# Complete_Power_Supply.net
KiCad netlist of a schematic drawn in Altium Designer
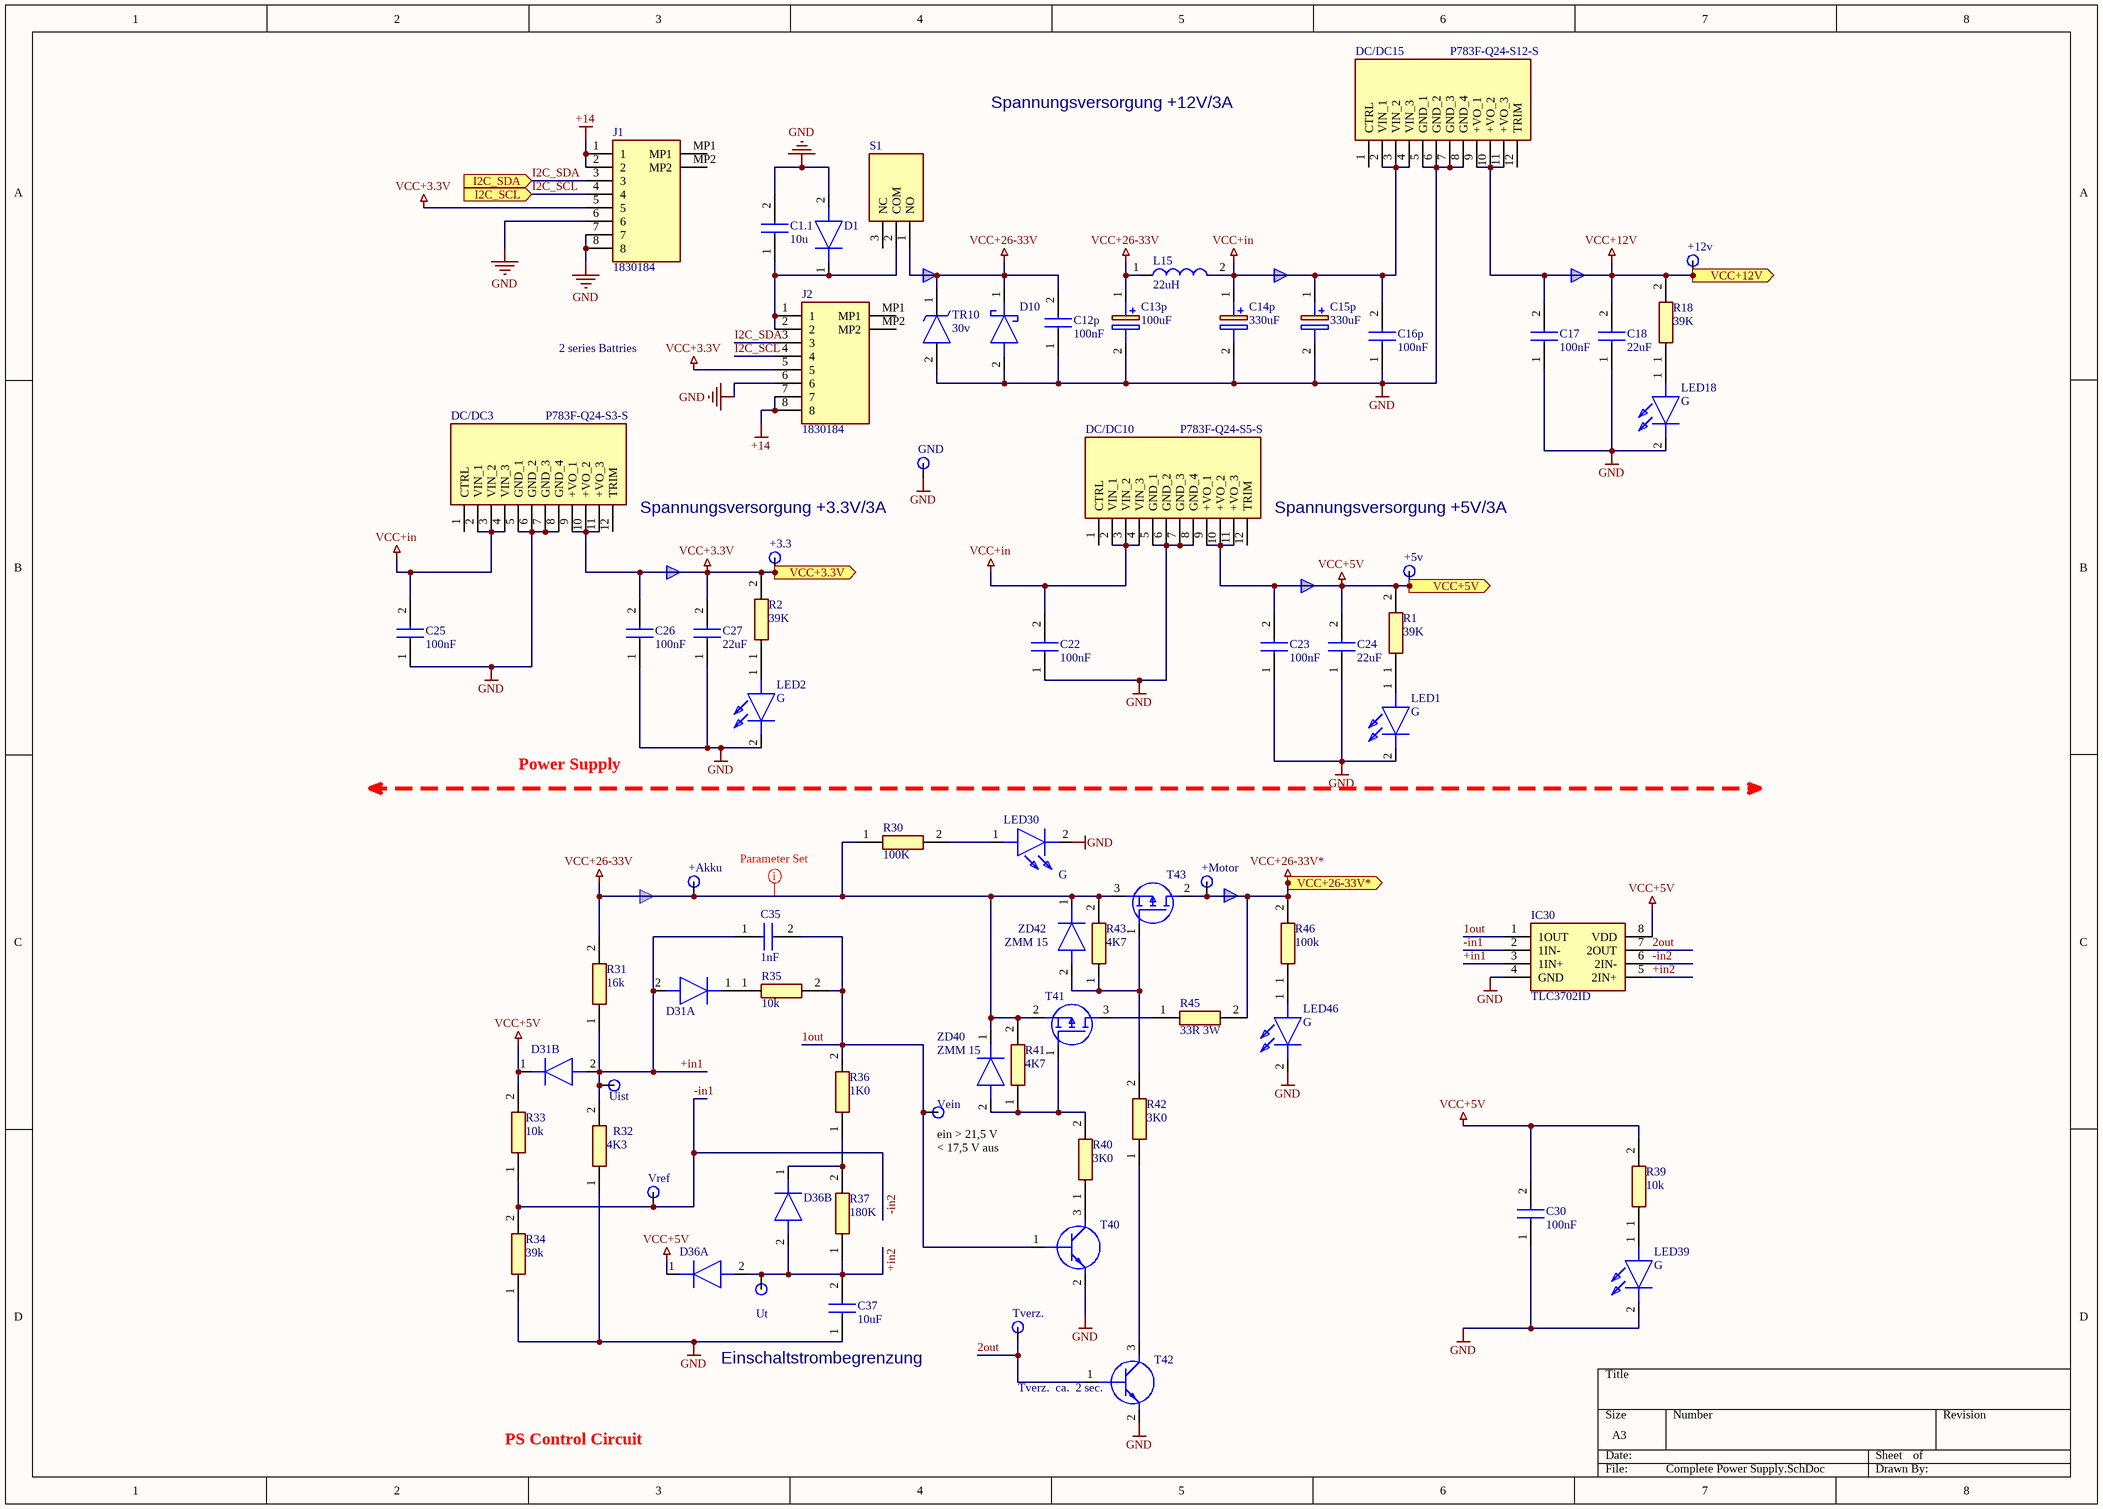
[diagram p0: Complete Power Supply.SchDoc]

(export (version "E")
  (design (tool "Eeschema 10.0.6"))
  (components
    (comp (ref "+3.3") (value "TP") (footprint "TP") (libsource (lib "tp sch lib") (part "TP")))
    (comp (ref "+5v") (value "TP") (footprint "TP") (libsource (lib "tp sch lib") (part "TP")))
    (comp (ref "+12v") (value "TP") (footprint "TP") (libsource (lib "tp sch lib") (part "TP")))
    (comp (ref "+Akku") (value "TP") (footprint "TP") (libsource (lib "tp sch lib") (part "TP")))
    (comp (ref "+Motor") (value "TP") (footprint "TP") (libsource (lib "tp sch lib") (part "TP")))
    (comp (ref "C1.1")
      (value "10u")
      (footprint "SamacSys:CAPC3216X180N")
      (description "Capacitor\r\nCL31A106KBHNNNE")
      (fields
        (field (name "MANUFACTURER_PART_NUMBER") "CL31A106KBHNNNE")
        (field (name "MOUSER PART NUMBER") "187-CL31A106KBHNNNE")
      )
      (libsource (lib "*") (part "CL31A106KBHNNNE"))
    )
    (comp (ref "C12p")
      (value "100nF")
      (footprint "SamacSys:CAPC1608X90N")
      (description "Capacitor\r\nGRM188R61E225KA12D\r\n0603")
      (fields
        (field (name "MANUFACTURER_PART_NUMBER") "GRM188R61E225KA12D")
        (field (name "MOUSER PART NUMBER") "81-GRM188R61E225KA2D")
      )
      (libsource (lib "SamacSys") (part "GRM188R61E225KA12D"))
    )
    (comp (ref "C13p")
      (value "100uF")
      (footprint "SamacSys:CAPPRD350W50D800H1750")
      (description "Capacitor Polarised")
      (fields (field (name "MANUFACTURER_PART_NUMBER") "860080274012"))
      (libsource (lib "*") (part "860080274012"))
    )
    (comp (ref "C14p")
      (value "330uF")
      (footprint "SamacSys:CAPPRD500W60D1050H1750")
      (description "Capacitor Polarised")
      (fields (field (name "MANUFACTURER_PART_NUMBER") "25YXF470M10X16"))
      (libsource (lib "*") (part "25YXF470M10X16"))
    )
    (comp (ref "C15p")
      (value "330uF")
      (footprint "SamacSys:CAPPRD500W60D1050H1750")
      (description "Capacitor Polarised")
      (fields (field (name "MANUFACTURER_PART_NUMBER") "25YXF470M10X16"))
      (libsource (lib "*") (part "25YXF470M10X16"))
    )
    (comp (ref "C16p")
      (value "100nF")
      (footprint "SamacSys:CAPC1608X90N")
      (description "Capacitor\r\nGRM188R61E225KA12D\r\n0603")
      (fields
        (field (name "MANUFACTURER_PART_NUMBER") "GRM188R61E225KA12D")
        (field (name "MOUSER PART NUMBER") "81-GRM188R61E225KA2D")
      )
      (libsource (lib "SamacSys") (part "GRM188R61E225KA12D"))
    )
    (comp (ref "C17")
      (value "100nF")
      (footprint "SamacSys:CAPC1608X90N")
      (description "Capacitor\r\nGRM188R61E225KA12D\r\n0603")
      (fields
        (field (name "MANUFACTURER_PART_NUMBER") "GRM188R61E225KA12D")
        (field (name "MOUSER PART NUMBER") "81-GRM188R61E225KA2D")
      )
      (libsource (lib "SamacSys") (part "GRM188R61E225KA12D"))
    )
    (comp (ref "C18")
      (value "22uF")
      (footprint "SamacSys:CAPC3216X180N")
      (description "Capacitor\r\nGRM31CR61H106MA12L\r\n1206")
      (fields
        (field (name "MANUFACTURER_PART_NUMBER") "GRM31CR61H106MA12L")
        (field (name "MOUSER PART NUMBER") "81-GRM31CR61H106MA2L")
      )
      (libsource (lib "SamacSys") (part "GRM31CR61H106MA12L"))
    )
    (comp (ref "C22")
      (value "100nF")
      (footprint "SamacSys:CAPC1608X90N")
      (description "Capacitor\r\nGRM188R61E225KA12D\r\n0603")
      (fields
        (field (name "MANUFACTURER_PART_NUMBER") "GRM188R61E225KA12D")
        (field (name "MOUSER PART NUMBER") "81-GRM188R61E225KA2D")
      )
      (libsource (lib "SamacSys") (part "GRM188R61E225KA12D"))
    )
    (comp (ref "C23")
      (value "100nF")
      (footprint "SamacSys:CAPC1608X90N")
      (description "Capacitor\r\nGRM188R61E225KA12D\r\n0603")
      (fields
        (field (name "MANUFACTURER_PART_NUMBER") "GRM188R61E225KA12D")
        (field (name "MOUSER PART NUMBER") "81-GRM188R61E225KA2D")
      )
      (libsource (lib "SamacSys") (part "GRM188R61E225KA12D"))
    )
    (comp (ref "C24")
      (value "22uF")
      (footprint "SamacSys:CAPC3216X180N")
      (description "Capacitor\r\nGRM31CR61H106MA12L\r\n1206")
      (fields
        (field (name "MANUFACTURER_PART_NUMBER") "GRM31CR61H106MA12L")
        (field (name "MOUSER PART NUMBER") "81-GRM31CR61H106MA2L")
      )
      (libsource (lib "SamacSys") (part "GRM31CR61H106MA12L"))
    )
    (comp (ref "C25")
      (value "100nF")
      (footprint "SamacSys:CAPC1608X90N")
      (description "Capacitor\r\nGRM188R61E225KA12D\r\n0603")
      (fields
        (field (name "MANUFACTURER_PART_NUMBER") "GRM188R61E225KA12D")
        (field (name "MOUSER PART NUMBER") "81-GRM188R61E225KA2D")
      )
      (libsource (lib "SamacSys") (part "GRM188R61E225KA12D"))
    )
    (comp (ref "C26")
      (value "100nF")
      (footprint "SamacSys:CAPC1608X90N")
      (description "Capacitor\r\nGRM188R61E225KA12D\r\n0603")
      (fields
        (field (name "MANUFACTURER_PART_NUMBER") "GRM188R61E225KA12D")
        (field (name "MOUSER PART NUMBER") "81-GRM188R61E225KA2D")
      )
      (libsource (lib "SamacSys") (part "GRM188R61E225KA12D"))
    )
    (comp (ref "C27")
      (value "22uF")
      (footprint "SamacSys:CAPC3216X180N")
      (description "Capacitor\r\nGRM31CR61H106MA12L\r\n1206")
      (fields
        (field (name "MANUFACTURER_PART_NUMBER") "GRM31CR61H106MA12L")
        (field (name "MOUSER PART NUMBER") "81-GRM31CR61H106MA2L")
      )
      (libsource (lib "SamacSys") (part "GRM31CR61H106MA12L"))
    )
    (comp (ref "C30")
      (value "100nF")
      (footprint "SamacSys:CAPC1608X90N")
      (description "Capacitor\r\nGRM188R61E225KA12D\r\n0603")
      (fields
        (field (name "MANUFACTURER_PART_NUMBER") "GRM188R61E225KA12D")
        (field (name "MOUSER PART NUMBER") "81-GRM188R61E225KA2D")
      )
      (libsource (lib "SamacSys") (part "GRM188R61E225KA12D"))
    )
    (comp (ref "C35")
      (value "1nF")
      (footprint "SamacSys:CAPC1608X90N")
      (description "Capacitor\r\nGRM188R61E225KA12D\r\n0603")
      (fields
        (field (name "MANUFACTURER_PART_NUMBER") "GRM188R61E225KA12D")
        (field (name "MOUSER PART NUMBER") "81-GRM188R61E225KA2D")
      )
      (libsource (lib "SamacSys") (part "GRM188R61E225KA12D"))
    )
    (comp (ref "C37")
      (value "10uF")
      (footprint "SamacSys:CAPC1608X90N")
      (description "Capacitor\r\nGRM188R61E225KA12D\r\n0603")
      (fields
        (field (name "MANUFACTURER_PART_NUMBER") "GRM188R61E225KA12D")
        (field (name "MOUSER PART NUMBER") "81-GRM188R61E225KA2D")
      )
      (libsource (lib "SamacSys") (part "GRM188R61E225KA12D"))
    )
    (comp (ref "D1")
      (value "SM6T39A")
      (footprint "SamacSys:SMBJ36CATR")
      (description "Diode")
      (fields (field (name "MOUSER PART NUMBER") "511-SM6T39A"))
      (libsource (lib "*") (part "SM6T39A"))
    )
    (comp (ref "D10")
      (value "~")
      (footprint "SamacSys:DIOM8059X295N")
      (description "Schottky Diode\r\n30BQ015TR")
      (fields (field (name "MANUFACTURER_PART_NUMBER") "30BQ015TR"))
      (libsource (lib "*") (part "30BQ015TR"))
    )
    (comp (ref "D31A")
      (value "BAS3010A03WE6327HTSA1")
      (footprint "SamacSys:SOD2513X110N")
      (description "Diode")
      (fields (field (name "MOUSER PART NUMBER") "726-BAS3010A-03WE6"))
      (libsource (lib "*") (part "BAS3010A03WE6327HTSA1"))
    )
    (comp (ref "D31B")
      (value "BAS3010A03WE6327HTSA1")
      (footprint "SamacSys:SOD2513X110N")
      (description "Diode")
      (fields (field (name "MOUSER PART NUMBER") "726-BAS3010A-03WE6"))
      (libsource (lib "*") (part "BAS3010A03WE6327HTSA1"))
    )
    (comp (ref "D36A")
      (value "BAS3010A03WE6327HTSA1")
      (footprint "SamacSys:SOD2513X110N")
      (description "Diode")
      (fields (field (name "MOUSER PART NUMBER") "726-BAS3010A-03WE6"))
      (libsource (lib "*") (part "BAS3010A03WE6327HTSA1"))
    )
    (comp (ref "D36B")
      (value "BAS3010A03WE6327HTSA1")
      (footprint "SamacSys:SOD2513X110N")
      (description "Diode")
      (fields (field (name "MOUSER PART NUMBER") "726-BAS3010A-03WE6"))
      (libsource (lib "*") (part "BAS3010A03WE6327HTSA1"))
    )
    (comp (ref "DC/DC3")
      (value "P783F-Q24-S3-S")
      (footprint "SamacSys:P783FQ24S12S")
      (description "Power Supply\r\nP783F-Q24-S12-S")
      (fields
        (field (name "MANUFACTURER_PART_NUMBER") "P783F-Q24-S12-S")
        (field (name "MOUSER PART NUMBER") "490-P783F-Q24-S12-S")
      )
      (libsource (lib "*") (part "P783F-Q24-S12-S"))
    )
    (comp (ref "DC/DC10")
      (value "P783F-Q24-S5-S")
      (footprint "SamacSys:P783FQ24S12S")
      (description "Power Supply\r\nP783F-Q24-S12-S")
      (fields
        (field (name "MANUFACTURER_PART_NUMBER") "P783F-Q24-S12-S")
        (field (name "MOUSER PART NUMBER") "490-P783F-Q24-S12-S")
      )
      (libsource (lib "*") (part "P783F-Q24-S12-S"))
    )
    (comp (ref "DC/DC15")
      (value "P783F-Q24-S12-S")
      (footprint "SamacSys:P783FQ24S12S")
      (description "Power Supply\r\nP783F-Q24-S12-S")
      (fields (field (name "MOUSER PART NUMBER") "490-P783F-Q24-S12-S"))
      (libsource (lib "*") (part "P783F-Q24-S12-S"))
    )
    (comp (ref "GND") (value "TP") (footprint "TP") (libsource (lib "tp sch lib") (part "TP")))
    (comp (ref "IC30")
      (value "TLC3702ID")
      (footprint "SamacSys:SOIC127P600X175-8N")
      (description "Integrated Circuit")
      (fields (field (name "MOUSER PART NUMBER") "595-TLC3702ID"))
      (libsource (lib "*") (part "TLC3702ID"))
    )
    (comp (ref "J1")
      (value "1830184")
      (footprint "SamacSys:1830184")
      (description "Connector")
      (fields (field (name "MOUSER PART NUMBER") "651-1830184"))
      (libsource (lib "*") (part "1830184"))
    )
    (comp (ref "J2")
      (value "1830184")
      (footprint "SamacSys:1830184")
      (description "Connector")
      (fields (field (name "MOUSER PART NUMBER") "651-1830184"))
      (libsource (lib "*") (part "1830184"))
    )
    (comp (ref "L15")
      (value "22uH")
      (footprint "SamacSys:INDPM7366X300N")
      (description "Inductor")
      (fields
        (field (name "MANUFACTURER_PART_NUMBER") "74437346068")
        (field (name "MOUSER PART NUMBER") "710-74437346068")
      )
      (libsource (lib "*") (part "74437346068"))
    )
    (comp (ref "LED1")
      (value "G")
      (footprint "SamacSys:KP2012SGD")
      (description "LED\r\nKP-2012SGD\r\n0805")
      (fields (field (name "MANUFACTURER_PART_NUMBER") "KP-2012SGD"))
      (libsource (lib "*") (part "KP-2012SGD"))
    )
    (comp (ref "LED2")
      (value "G")
      (footprint "SamacSys:KP2012SGD")
      (description "LED\r\nKP-2012SGD\r\n0805")
      (fields (field (name "MANUFACTURER_PART_NUMBER") "KP-2012SGD"))
      (libsource (lib "*") (part "KP-2012SGD"))
    )
    (comp (ref "LED18")
      (value "G")
      (footprint "SamacSys:KP2012SGD")
      (description "LED\r\nKP-2012SGD\r\n0805")
      (fields (field (name "MANUFACTURER_PART_NUMBER") "KP-2012SGD"))
      (libsource (lib "*") (part "KP-2012SGD"))
    )
    (comp (ref "LED30")
      (value "G")
      (footprint "SamacSys:KP2012SGD")
      (description "LED\r\nKP-2012SGD\r\n0805")
      (fields (field (name "MANUFACTURER_PART_NUMBER") "KP-2012SGD"))
      (libsource (lib "*") (part "KP-2012SGD"))
    )
    (comp (ref "LED39")
      (value "G")
      (footprint "SamacSys:KP2012SGD")
      (description "LED\r\nKP-2012SGD\r\n0805")
      (fields (field (name "MANUFACTURER_PART_NUMBER") "KP-2012SGD"))
      (libsource (lib "*") (part "KP-2012SGD"))
    )
    (comp (ref "LED46")
      (value "G")
      (footprint "SamacSys:KP2012SGD")
      (description "LED\r\nKP-2012SGD\r\n0805")
      (fields (field (name "MANUFACTURER_PART_NUMBER") "KP-2012SGD"))
      (libsource (lib "*") (part "KP-2012SGD"))
    )
    (comp (ref "R1")
      (value "39K")
      (footprint "SamacSys:RESC2012X65N")
      (description "Resistor\r\nCPF0805B100RE1\r\n0805")
      (fields
        (field (name "MANUFACTURER_PART_NUMBER") "CPF0805B100RE1")
        (field (name "MOUSER PART NUMBER") "279-CPF0805B100RE1")
      )
      (libsource (lib "") (part "CPF0805B100RE1_1"))
    )
    (comp (ref "R2")
      (value "39K")
      (footprint "SamacSys:RESC2012X65N")
      (description "Resistor\r\nCPF0805B100RE1\r\n0805")
      (fields
        (field (name "MANUFACTURER_PART_NUMBER") "CPF0805B100RE1")
        (field (name "MOUSER PART NUMBER") "279-CPF0805B100RE1")
      )
      (libsource (lib "") (part "CPF0805B100RE1_1"))
    )
    (comp (ref "R18")
      (value "39K")
      (footprint "SamacSys:RESC2012X65N")
      (description "Resistor\r\nCPF0805B100RE1\r\n0805")
      (fields
        (field (name "MANUFACTURER_PART_NUMBER") "CPF0805B100RE1")
        (field (name "MOUSER PART NUMBER") "279-CPF0805B100RE1")
      )
      (libsource (lib "") (part "CPF0805B100RE1_1"))
    )
    (comp (ref "R30")
      (value "100K")
      (footprint "SamacSys:RESC2012X65N")
      (description "Resistor\r\nCPF0805B100RE1\r\n0805")
      (fields
        (field (name "MANUFACTURER_PART_NUMBER") "CPF0805B100RE1")
        (field (name "MOUSER PART NUMBER") "279-CPF0805B100RE1")
      )
      (libsource (lib "*") (part "CPF0805B100RE1"))
    )
    (comp (ref "R31")
      (value "16k")
      (footprint "SamacSys:RESC1608X60N")
      (description "Resistor\r\n0603")
      (fields (field (name "MANUFACTURER_PART_NUMBER") "MCSR06X47R0FTL"))
      (libsource (lib "SamacSys") (part "MCSR06X47R0FTL"))
    )
    (comp (ref "R32")
      (value "4K3")
      (footprint "SamacSys:RESC1608X60N")
      (description "Resistor\r\n0603")
      (fields (field (name "MANUFACTURER_PART_NUMBER") "MCSR06X47R0FTL"))
      (libsource (lib "SamacSys") (part "MCSR06X47R0FTL"))
    )
    (comp (ref "R33")
      (value "10k")
      (footprint "SamacSys:RESC1608X60N")
      (description "Resistor\r\n0603")
      (fields (field (name "MANUFACTURER_PART_NUMBER") "MCSR06X47R0FTL"))
      (libsource (lib "SamacSys") (part "MCSR06X47R0FTL"))
    )
    (comp (ref "R34")
      (value "39k")
      (footprint "SamacSys:RESC1608X60N")
      (description "Resistor\r\n0603")
      (fields (field (name "MANUFACTURER_PART_NUMBER") "MCSR06X47R0FTL"))
      (libsource (lib "SamacSys") (part "MCSR06X47R0FTL"))
    )
    (comp (ref "R35")
      (value "10k")
      (footprint "SamacSys:RESC1608X60N")
      (description "Resistor\r\n0603")
      (fields (field (name "MANUFACTURER_PART_NUMBER") "MCSR06X47R0FTL"))
      (libsource (lib "") (part "MCSR06X47R0FTL_1"))
    )
    (comp (ref "R36")
      (value "1K0")
      (footprint "SamacSys:RESC1608X60N")
      (description "Resistor\r\n0603")
      (fields (field (name "MANUFACTURER_PART_NUMBER") "MCSR06X47R0FTL"))
      (libsource (lib "SamacSys") (part "MCSR06X47R0FTL"))
    )
    (comp (ref "R37")
      (value "180K")
      (footprint "SamacSys:RESC1608X60N")
      (description "Resistor\r\n0603")
      (fields (field (name "MANUFACTURER_PART_NUMBER") "MCSR06X47R0FTL"))
      (libsource (lib "SamacSys") (part "MCSR06X47R0FTL"))
    )
    (comp (ref "R39")
      (value "10k")
      (footprint "SamacSys:RESC2012X65N")
      (description "Resistor\r\nCPF0805B100RE1\r\n0805")
      (fields
        (field (name "MANUFACTURER_PART_NUMBER") "CPF0805B100RE1")
        (field (name "MOUSER PART NUMBER") "279-CPF0805B100RE1")
      )
      (libsource (lib "") (part "CPF0805B100RE1_1"))
    )
    (comp (ref "R40")
      (value "3K0")
      (footprint "SamacSys:RESC1608X60N")
      (description "Resistor\r\n0603")
      (fields (field (name "MANUFACTURER_PART_NUMBER") "MCSR06X47R0FTL"))
      (libsource (lib "SamacSys") (part "MCSR06X47R0FTL"))
    )
    (comp (ref "R41")
      (value "4K7")
      (footprint "SamacSys:RESC1608X60N")
      (description "Resistor\r\n0603")
      (fields (field (name "MANUFACTURER_PART_NUMBER") "MCSR06X47R0FTL"))
      (libsource (lib "SamacSys") (part "MCSR06X47R0FTL"))
    )
    (comp (ref "R42")
      (value "3K0")
      (footprint "SamacSys:RESC1608X60N")
      (description "Resistor\r\n0603")
      (fields (field (name "MANUFACTURER_PART_NUMBER") "MCSR06X47R0FTL"))
      (libsource (lib "SamacSys") (part "MCSR06X47R0FTL"))
    )
    (comp (ref "R43")
      (value "4K7")
      (footprint "SamacSys:RESC1608X60N")
      (description "Resistor\r\n0603")
      (fields (field (name "MANUFACTURER_PART_NUMBER") "MCSR06X47R0FTL"))
      (libsource (lib "SamacSys") (part "MCSR06X47R0FTL"))
    )
    (comp (ref "R45")
      (value "33R 3W")
      (footprint "SamacSys:ERJ8_B_BW_R_LW_CW_D")
      (description "Resistor\r\n1206\r\n33R 3W")
      (fields
        (field (name "MANUFACTURER_PART_NUMBER") "ERJ-8BWFR075V")
        (field (name "MOUSER PART NUMBER") "667-ERJ-8BWFR075V")
      )
      (libsource (lib "SamacSys") (part "ERJ-8BWFR075V"))
    )
    (comp (ref "R46")
      (value "100k")
      (footprint "SamacSys:RESC2012X65N")
      (description "Resistor\r\nCPF0805B100RE1\r\n0805")
      (fields
        (field (name "MANUFACTURER_PART_NUMBER") "CPF0805B100RE1")
        (field (name "MOUSER PART NUMBER") "279-CPF0805B100RE1")
      )
      (libsource (lib "") (part "CPF0805B100RE1_1"))
    )
    (comp (ref "S1")
      (value "1-1825137-1")
      (footprint "SamacSys:118251371")
      (description "Switch single pole single throw")
      (libsource (lib "*") (part "1-1825137-1"))
    )
    (comp (ref "T40")
      (value "BCR135WH6327XTSA1")
      (footprint "SamacSys:SOT65P210X100-3N")
      (description "Digitaltransistor, npn, 50V, 100mA, SOT23")
      (fields (field (name "MOUSER PART NUMBER") "726-BCR135WH6327XTSA"))
      (libsource (lib "*") (part "BCR135WH6327XTSA1"))
    )
    (comp (ref "T41")
      (value "AO3407A")
      (footprint "SamacSys:SOT95P280X125-3N")
      (description "MOS-FET, p-Kanal, -40  V, -3,4 A, SOT23")
      (libsource (lib "*") (part "AO3407A"))
    )
    (comp (ref "T42")
      (value "BCR135WH6327XTSA1")
      (footprint "SamacSys:SOT65P210X100-3N")
      (description "Digitaltransistor, npn, 50V, 100mA, SOT23")
      (fields (field (name "MOUSER PART NUMBER") "726-BCR135WH6327XTSA"))
      (libsource (lib "*") (part "BCR135WH6327XTSA1"))
    )
    (comp (ref "T43")
      (value "AUIRF9Z34N")
      (footprint "SamacSys:TO254P482X1016X2192-3P")
      (description "MOS-FET, p-Kanal, -40  V, -120 A, TO220")
      (fields (field (name "MOUSER PART NUMBER") "942-AUIRF9Z34N"))
      (libsource (lib "*") (part "AUIRF9Z34N"))
    )
    (comp (ref "TR10")
      (value "30v")
      (footprint "SamacSys:DIOM7959X262N")
      (description "Überspannungsdiode, 30 V, 3000 W, DO214-AB, unidirektional, SMD")
      (fields
        (field (name "MANUFACTURER_PART_NUMBER") "1.5SMC15A")
        (field (name "MOUSER PART NUMBER") "576-1.5SMC15A")
      )
      (libsource (lib "*") (part "1.5SMC15A"))
    )
    (comp (ref "Tverz.") (value "TP") (footprint "TP") (libsource (lib "tp sch lib") (part "TP")))
    (comp (ref "Uist") (value "TP") (footprint "TP") (libsource (lib "tp sch lib") (part "TP")))
    (comp (ref "Ut") (value "TP") (footprint "TP") (libsource (lib "tp sch lib") (part "TP")))
    (comp (ref "Vein") (value "TP") (footprint "TP") (libsource (lib "tp sch lib") (part "TP")))
    (comp (ref "Vref") (value "TP") (footprint "TP") (libsource (lib "tp sch lib") (part "TP")))
    (comp (ref "ZD40")
      (value "ZMM 15")
      (footprint "SamacSys:BZT55B13GS08")
      (description "SOD-80\r\nZMM 15, 5%")
      (fields
        (field (name "MANUFACTURER_PART_NUMBER") "LS4150GS08")
        (field (name "MOUSER PART NUMBER") "78-LS4150")
      )
      (libsource (lib "*") (part "LS4150GS08"))
    )
    (comp (ref "ZD42")
      (value "ZMM 15")
      (footprint "SamacSys:BZT55B13GS08")
      (description "SOD-80\r\nZMM 15, 5%")
      (fields
        (field (name "MANUFACTURER_PART_NUMBER") "LS4150GS08")
        (field (name "MOUSER PART NUMBER") "78-LS4150")
      )
      (libsource (lib "*") (part "LS4150GS08"))
    )
  )
  (nets
    (net (code "1") (name "+14") (class "Default")
      (node (ref "J1") (pin "1") (pinfunction "1_1") (pintype "passive"))
      (node (ref "J1") (pin "2") (pinfunction "2_2") (pintype "passive"))
      (node (ref "J2") (pin "7") (pinfunction "7_7") (pintype "passive"))
      (node (ref "J2") (pin "8") (pinfunction "8_8") (pintype "passive"))
    )
    (net (code "2") (name "/+in1") (class "Default")
      (node (ref "C35") (pin "1") (pinfunction "1_1") (pintype "passive"))
      (node (ref "D31A") (pin "2") (pinfunction "A_2") (pintype "passive"))
      (node (ref "D31B") (pin "2") (pinfunction "A_2") (pintype "passive"))
      (node (ref "IC30") (pin "3") (pinfunction "1IN+_3") (pintype "passive"))
      (node (ref "R31") (pin "1") (pinfunction "1_1") (pintype "passive"))
      (node (ref "R32") (pin "2") (pinfunction "2_2") (pintype "passive"))
      (node (ref "Uist") (pin "25") (pinfunction "25_25") (pintype "passive"))
    )
    (net (code "3") (name "/+in2") (class "Default")
      (node (ref "C37") (pin "2") (pinfunction "2_2") (pintype "passive"))
      (node (ref "D36A") (pin "2") (pinfunction "A_2") (pintype "passive"))
      (node (ref "D36B") (pin "2") (pinfunction "A_2") (pintype "passive"))
      (node (ref "IC30") (pin "5") (pinfunction "2IN+_5") (pintype "passive"))
      (node (ref "R37") (pin "1") (pinfunction "1_1") (pintype "passive"))
      (node (ref "Ut") (pin "25") (pinfunction "25_25") (pintype "passive"))
    )
    (net (code "4") (name "/-in1") (class "Default")
      (node (ref "IC30") (pin "2") (pinfunction "1IN-_2") (pintype "passive"))
      (node (ref "IC30") (pin "6") (pinfunction "2IN-_6") (pintype "passive"))
      (node (ref "R33") (pin "1") (pinfunction "1_1") (pintype "passive"))
      (node (ref "R34") (pin "2") (pinfunction "2_2") (pintype "passive"))
      (node (ref "Vref") (pin "25") (pinfunction "25_25") (pintype "passive"))
    )
    (net (code "5") (name "/1out") (class "Default")
      (node (ref "C35") (pin "2") (pinfunction "2_2") (pintype "passive"))
      (node (ref "IC30") (pin "1") (pinfunction "1OUT_1") (pintype "passive"))
      (node (ref "R35") (pin "2") (pinfunction "2_2") (pintype "passive"))
      (node (ref "R36") (pin "2") (pinfunction "2_2") (pintype "passive"))
      (node (ref "T40") (pin "1") (pinfunction "B_1") (pintype "passive"))
      (node (ref "Vein") (pin "25") (pinfunction "25_25") (pintype "passive"))
    )
    (net (code "6") (name "/2out") (class "Default")
      (node (ref "IC30") (pin "7") (pinfunction "2OUT_7") (pintype "passive"))
      (node (ref "T42") (pin "1") (pinfunction "B_1") (pintype "passive"))
      (node (ref "Tverz.") (pin "25") (pinfunction "25_25") (pintype "passive"))
    )
    (net (code "7") (name "/I2C_SCL") (class "Default")
      (node (ref "J1") (pin "4") (pinfunction "4_4") (pintype "passive"))
      (node (ref "J2") (pin "4") (pinfunction "4_4") (pintype "passive"))
    )
    (net (code "8") (name "/I2C_SDA") (class "Default")
      (node (ref "J1") (pin "3") (pinfunction "3_3") (pintype "passive"))
      (node (ref "J2") (pin "3") (pinfunction "3_3") (pintype "passive"))
    )
    (net (code "9") (name "GND") (class "Default")
      (node (ref "C1.1") (pin "2") (pinfunction "2_2") (pintype "passive"))
      (node (ref "C12p") (pin "1") (pinfunction "1_1") (pintype "passive"))
      (node (ref "C13p") (pin "2") (pinfunction "-_2") (pintype "passive"))
      (node (ref "C14p") (pin "2") (pinfunction "-_2") (pintype "passive"))
      (node (ref "C15p") (pin "2") (pinfunction "-_2") (pintype "passive"))
      (node (ref "C16p") (pin "1") (pinfunction "1_1") (pintype "passive"))
      (node (ref "C17") (pin "1") (pinfunction "1_1") (pintype "passive"))
      (node (ref "C18") (pin "1") (pinfunction "1_1") (pintype "passive"))
      (node (ref "C22") (pin "1") (pinfunction "1_1") (pintype "passive"))
      (node (ref "C23") (pin "1") (pinfunction "1_1") (pintype "passive"))
      (node (ref "C24") (pin "1") (pinfunction "1_1") (pintype "passive"))
      (node (ref "C25") (pin "1") (pinfunction "1_1") (pintype "passive"))
      (node (ref "C26") (pin "1") (pinfunction "1_1") (pintype "passive"))
      (node (ref "C27") (pin "1") (pinfunction "1_1") (pintype "passive"))
      (node (ref "C30") (pin "1") (pinfunction "1_1") (pintype "passive"))
      (node (ref "C37") (pin "1") (pinfunction "1_1") (pintype "passive"))
      (node (ref "D1") (pin "2") (pinfunction "A_2") (pintype "passive"))
      (node (ref "D10") (pin "2") (pinfunction "A_2") (pintype "passive"))
      (node (ref "DC/DC10") (pin "5") (pinfunction "GND_1_5") (pintype "passive"))
      (node (ref "DC/DC10") (pin "6") (pinfunction "GND_2_6") (pintype "passive"))
      (node (ref "DC/DC10") (pin "7") (pinfunction "GND_3_7") (pintype "passive"))
      (node (ref "DC/DC10") (pin "8") (pinfunction "GND_4_8") (pintype "passive"))
      (node (ref "DC/DC15") (pin "5") (pinfunction "GND_1_5") (pintype "passive"))
      (node (ref "DC/DC15") (pin "6") (pinfunction "GND_2_6") (pintype "passive"))
      (node (ref "DC/DC15") (pin "7") (pinfunction "GND_3_7") (pintype "passive"))
      (node (ref "DC/DC15") (pin "8") (pinfunction "GND_4_8") (pintype "passive"))
      (node (ref "DC/DC3") (pin "5") (pinfunction "GND_1_5") (pintype "passive"))
      (node (ref "DC/DC3") (pin "6") (pinfunction "GND_2_6") (pintype "passive"))
      (node (ref "DC/DC3") (pin "7") (pinfunction "GND_3_7") (pintype "passive"))
      (node (ref "DC/DC3") (pin "8") (pinfunction "GND_4_8") (pintype "passive"))
      (node (ref "GND") (pin "25") (pinfunction "25_25") (pintype "passive"))
      (node (ref "IC30") (pin "4") (pinfunction "GND_4") (pintype "passive"))
      (node (ref "J1") (pin "6") (pinfunction "6_6") (pintype "passive"))
      (node (ref "J1") (pin "7") (pinfunction "7_7") (pintype "passive"))
      (node (ref "J1") (pin "8") (pinfunction "8_8") (pintype "passive"))
      (node (ref "J2") (pin "6") (pinfunction "6_6") (pintype "passive"))
      (node (ref "LED1") (pin "2") (pinfunction "K_2") (pintype "passive"))
      (node (ref "LED18") (pin "2") (pinfunction "K_2") (pintype "passive"))
      (node (ref "LED2") (pin "2") (pinfunction "K_2") (pintype "passive"))
      (node (ref "LED30") (pin "2") (pinfunction "K_2") (pintype "passive"))
      (node (ref "LED39") (pin "2") (pinfunction "K_2") (pintype "passive"))
      (node (ref "LED46") (pin "2") (pinfunction "K_2") (pintype "passive"))
      (node (ref "R32") (pin "1") (pinfunction "1_1") (pintype "passive"))
      (node (ref "R34") (pin "1") (pinfunction "1_1") (pintype "passive"))
      (node (ref "T40") (pin "2") (pinfunction "E_2") (pintype "passive"))
      (node (ref "T42") (pin "2") (pinfunction "E_2") (pintype "passive"))
      (node (ref "TR10") (pin "2") (pinfunction "A_2") (pintype "passive"))
    )
    (net (code "10") (name "Net-(D1-K)") (class "Default")
      (node (ref "C1.1") (pin "1") (pinfunction "1_1") (pintype "passive"))
      (node (ref "D1") (pin "1") (pinfunction "K_1") (pintype "passive"))
      (node (ref "J2") (pin "1") (pinfunction "1_1") (pintype "passive"))
      (node (ref "J2") (pin "2") (pinfunction "2_2") (pintype "passive"))
      (node (ref "S1") (pin "2") (pinfunction "COM_2") (pintype "passive"))
    )
    (net (code "11") (name "Net-(D31A-K)") (class "Default")
      (node (ref "D31A") (pin "1") (pinfunction "K_1") (pintype "passive"))
      (node (ref "R35") (pin "1") (pinfunction "1_1") (pintype "passive"))
    )
    (net (code "12") (name "Net-(D36B-K)") (class "Default")
      (node (ref "D36B") (pin "1") (pinfunction "K_1") (pintype "passive"))
      (node (ref "R36") (pin "1") (pinfunction "1_1") (pintype "passive"))
      (node (ref "R37") (pin "2") (pinfunction "2_2") (pintype "passive"))
    )
    (net (code "13") (name "Net-(LED1-A)") (class "Default")
      (node (ref "LED1") (pin "1") (pinfunction "A_1") (pintype "passive"))
      (node (ref "R1") (pin "1") (pinfunction "1_1") (pintype "passive"))
    )
    (net (code "14") (name "Net-(LED2-A)") (class "Default")
      (node (ref "LED2") (pin "1") (pinfunction "A_1") (pintype "passive"))
      (node (ref "R2") (pin "1") (pinfunction "1_1") (pintype "passive"))
    )
    (net (code "15") (name "Net-(LED18-A)") (class "Default")
      (node (ref "LED18") (pin "1") (pinfunction "A_1") (pintype "passive"))
      (node (ref "R18") (pin "1") (pinfunction "1_1") (pintype "passive"))
    )
    (net (code "16") (name "Net-(LED30-A)") (class "Default")
      (node (ref "LED30") (pin "1") (pinfunction "A_1") (pintype "passive"))
      (node (ref "R30") (pin "2") (pinfunction "2_2") (pintype "passive"))
    )
    (net (code "17") (name "Net-(LED39-A)") (class "Default")
      (node (ref "LED39") (pin "1") (pinfunction "A_1") (pintype "passive"))
      (node (ref "R39") (pin "1") (pinfunction "1_1") (pintype "passive"))
    )
    (net (code "18") (name "Net-(LED46-A)") (class "Default")
      (node (ref "LED46") (pin "1") (pinfunction "A_1") (pintype "passive"))
      (node (ref "R46") (pin "1") (pinfunction "1_1") (pintype "passive"))
    )
    (net (code "19") (name "Net-(T40-C)") (class "Default")
      (node (ref "R40") (pin "1") (pinfunction "1_1") (pintype "passive"))
      (node (ref "T40") (pin "3") (pinfunction "C_3") (pintype "passive"))
    )
    (net (code "20") (name "Net-(T41-D)") (class "Default")
      (node (ref "R45") (pin "1") (pinfunction "1_1") (pintype "passive"))
      (node (ref "T41") (pin "3") (pinfunction "D_3") (pintype "passive"))
    )
    (net (code "21") (name "Net-(T41-G)") (class "Default")
      (node (ref "R40") (pin "2") (pinfunction "2_2") (pintype "passive"))
      (node (ref "R41") (pin "1") (pinfunction "1_1") (pintype "passive"))
      (node (ref "T41") (pin "1") (pinfunction "G_1") (pintype "passive"))
      (node (ref "ZD40") (pin "2") (pinfunction "A_2") (pintype "passive"))
    )
    (net (code "22") (name "Net-(T42-C)") (class "Default")
      (node (ref "R42") (pin "1") (pinfunction "1_1") (pintype "passive"))
      (node (ref "T42") (pin "3") (pinfunction "C_3") (pintype "passive"))
    )
    (net (code "23") (name "Net-(T43-G)") (class "Default")
      (node (ref "R42") (pin "2") (pinfunction "2_2") (pintype "passive"))
      (node (ref "R43") (pin "1") (pinfunction "1_1") (pintype "passive"))
      (node (ref "T43") (pin "1") (pinfunction "G_1") (pintype "passive"))
      (node (ref "ZD42") (pin "2") (pinfunction "A_2") (pintype "passive"))
    )
    (net (code "24") (name "VCC+3.3V") (class "Default")
      (node (ref "+3.3") (pin "25") (pinfunction "25_25") (pintype "passive"))
      (node (ref "C26") (pin "2") (pinfunction "2_2") (pintype "passive"))
      (node (ref "C27") (pin "2") (pinfunction "2_2") (pintype "passive"))
      (node (ref "DC/DC3") (pin "10") (pinfunction "+VO_2_10") (pintype "passive"))
      (node (ref "DC/DC3") (pin "11") (pinfunction "+VO_3_11") (pintype "passive"))
      (node (ref "DC/DC3") (pin "9") (pinfunction "+VO_1_9") (pintype "passive"))
      (node (ref "J1") (pin "5") (pinfunction "5_5") (pintype "passive"))
      (node (ref "J2") (pin "5") (pinfunction "5_5") (pintype "passive"))
      (node (ref "R2") (pin "2") (pinfunction "2_2") (pintype "passive"))
    )
    (net (code "25") (name "VCC+5V") (class "Default")
      (node (ref "+5v") (pin "25") (pinfunction "25_25") (pintype "passive"))
      (node (ref "C23") (pin "2") (pinfunction "2_2") (pintype "passive"))
      (node (ref "C24") (pin "2") (pinfunction "2_2") (pintype "passive"))
      (node (ref "C30") (pin "2") (pinfunction "2_2") (pintype "passive"))
      (node (ref "D31B") (pin "1") (pinfunction "K_1") (pintype "passive"))
      (node (ref "D36A") (pin "1") (pinfunction "K_1") (pintype "passive"))
      (node (ref "DC/DC10") (pin "10") (pinfunction "+VO_2_10") (pintype "passive"))
      (node (ref "DC/DC10") (pin "11") (pinfunction "+VO_3_11") (pintype "passive"))
      (node (ref "DC/DC10") (pin "9") (pinfunction "+VO_1_9") (pintype "passive"))
      (node (ref "IC30") (pin "8") (pinfunction "VDD_8") (pintype "passive"))
      (node (ref "R1") (pin "2") (pinfunction "2_2") (pintype "passive"))
      (node (ref "R33") (pin "2") (pinfunction "2_2") (pintype "passive"))
      (node (ref "R39") (pin "2") (pinfunction "2_2") (pintype "passive"))
    )
    (net (code "26") (name "VCC+12V") (class "Default")
      (node (ref "+12v") (pin "25") (pinfunction "25_25") (pintype "passive"))
      (node (ref "C17") (pin "2") (pinfunction "2_2") (pintype "passive"))
      (node (ref "C18") (pin "2") (pinfunction "2_2") (pintype "passive"))
      (node (ref "DC/DC15") (pin "10") (pinfunction "+VO_2_10") (pintype "passive"))
      (node (ref "DC/DC15") (pin "11") (pinfunction "+VO_3_11") (pintype "passive"))
      (node (ref "DC/DC15") (pin "9") (pinfunction "+VO_1_9") (pintype "passive"))
      (node (ref "R18") (pin "2") (pinfunction "2_2") (pintype "passive"))
    )
    (net (code "27") (name "VCC+26-33V") (class "Default")
      (node (ref "+Akku") (pin "25") (pinfunction "25_25") (pintype "passive"))
      (node (ref "C12p") (pin "2") (pinfunction "2_2") (pintype "passive"))
      (node (ref "C13p") (pin "1") (pinfunction "+_1") (pintype "passive"))
      (node (ref "D10") (pin "1") (pinfunction "K_1") (pintype "passive"))
      (node (ref "L15") (pin "1") (pinfunction "1_1") (pintype "passive"))
      (node (ref "R30") (pin "1") (pinfunction "1_1") (pintype "passive"))
      (node (ref "R31") (pin "2") (pinfunction "2_2") (pintype "passive"))
      (node (ref "R41") (pin "2") (pinfunction "2_2") (pintype "passive"))
      (node (ref "R43") (pin "2") (pinfunction "2_2") (pintype "passive"))
      (node (ref "S1") (pin "1") (pinfunction "NO_1") (pintype "passive"))
      (node (ref "T41") (pin "2") (pinfunction "S_2") (pintype "passive"))
      (node (ref "T43") (pin "3") (pinfunction "S_3") (pintype "passive"))
      (node (ref "TR10") (pin "1") (pinfunction "K_1") (pintype "passive"))
      (node (ref "ZD40") (pin "1") (pinfunction "K_1") (pintype "passive"))
      (node (ref "ZD42") (pin "1") (pinfunction "K_1") (pintype "passive"))
    )
    (net (code "28") (name "VCC+26-33V*") (class "Default")
      (node (ref "+Motor") (pin "25") (pinfunction "25_25") (pintype "passive"))
      (node (ref "R45") (pin "2") (pinfunction "2_2") (pintype "passive"))
      (node (ref "R46") (pin "2") (pinfunction "2_2") (pintype "passive"))
      (node (ref "T43") (pin "2") (pinfunction "D_2") (pintype "passive"))
    )
    (net (code "29") (name "VCC+in") (class "Default")
      (node (ref "C14p") (pin "1") (pinfunction "+_1") (pintype "passive"))
      (node (ref "C15p") (pin "1") (pinfunction "+_1") (pintype "passive"))
      (node (ref "C16p") (pin "2") (pinfunction "2_2") (pintype "passive"))
      (node (ref "C22") (pin "2") (pinfunction "2_2") (pintype "passive"))
      (node (ref "C25") (pin "2") (pinfunction "2_2") (pintype "passive"))
      (node (ref "DC/DC10") (pin "2") (pinfunction "VIN_1_2") (pintype "passive"))
      (node (ref "DC/DC10") (pin "3") (pinfunction "VIN_2_3") (pintype "passive"))
      (node (ref "DC/DC10") (pin "4") (pinfunction "VIN_3_4") (pintype "passive"))
      (node (ref "DC/DC15") (pin "2") (pinfunction "VIN_1_2") (pintype "passive"))
      (node (ref "DC/DC15") (pin "3") (pinfunction "VIN_2_3") (pintype "passive"))
      (node (ref "DC/DC15") (pin "4") (pinfunction "VIN_3_4") (pintype "passive"))
      (node (ref "DC/DC3") (pin "2") (pinfunction "VIN_1_2") (pintype "passive"))
      (node (ref "DC/DC3") (pin "3") (pinfunction "VIN_2_3") (pintype "passive"))
      (node (ref "DC/DC3") (pin "4") (pinfunction "VIN_3_4") (pintype "passive"))
      (node (ref "L15") (pin "2") (pinfunction "2_2") (pintype "passive"))
    )
    (net (code "30") (name "unconnected-(DC/DC3-CTRL-Pad1)") (class "Default")
      (node (ref "DC/DC3") (pin "1") (pinfunction "CTRL_1") (pintype "passive"))
    )
    (net (code "31") (name "unconnected-(DC/DC3-TRIM-Pad12)") (class "Default")
      (node (ref "DC/DC3") (pin "12") (pinfunction "TRIM_12") (pintype "passive"))
    )
    (net (code "32") (name "unconnected-(DC/DC10-CTRL-Pad1)") (class "Default")
      (node (ref "DC/DC10") (pin "1") (pinfunction "CTRL_1") (pintype "passive"))
    )
    (net (code "33") (name "unconnected-(DC/DC10-TRIM-Pad12)") (class "Default")
      (node (ref "DC/DC10") (pin "12") (pinfunction "TRIM_12") (pintype "passive"))
    )
    (net (code "34") (name "unconnected-(DC/DC15-CTRL-Pad1)") (class "Default")
      (node (ref "DC/DC15") (pin "1") (pinfunction "CTRL_1") (pintype "passive"))
    )
    (net (code "35") (name "unconnected-(DC/DC15-TRIM-Pad12)") (class "Default")
      (node (ref "DC/DC15") (pin "12") (pinfunction "TRIM_12") (pintype "passive"))
    )
    (net (code "36") (name "unconnected-(J1-PadMP1)") (class "Default")
      (node (ref "J1") (pin "MP1") (pinfunction "MP1_MP1") (pintype "passive"))
    )
    (net (code "37") (name "unconnected-(J1-PadMP2)") (class "Default")
      (node (ref "J1") (pin "MP2") (pinfunction "MP2_MP2") (pintype "passive"))
    )
    (net (code "38") (name "unconnected-(J2-PadMP1)") (class "Default")
      (node (ref "J2") (pin "MP1") (pinfunction "MP1_MP1") (pintype "passive"))
    )
    (net (code "39") (name "unconnected-(J2-PadMP2)") (class "Default")
      (node (ref "J2") (pin "MP2") (pinfunction "MP2_MP2") (pintype "passive"))
    )
    (net (code "40") (name "unconnected-(S1-NC-Pad3)") (class "Default")
      (node (ref "S1") (pin "3") (pinfunction "NC_3") (pintype "passive"))
    )
  )
)
